# Digital_Inputs.net
KiCad netlist of a schematic drawn in Altium Designer
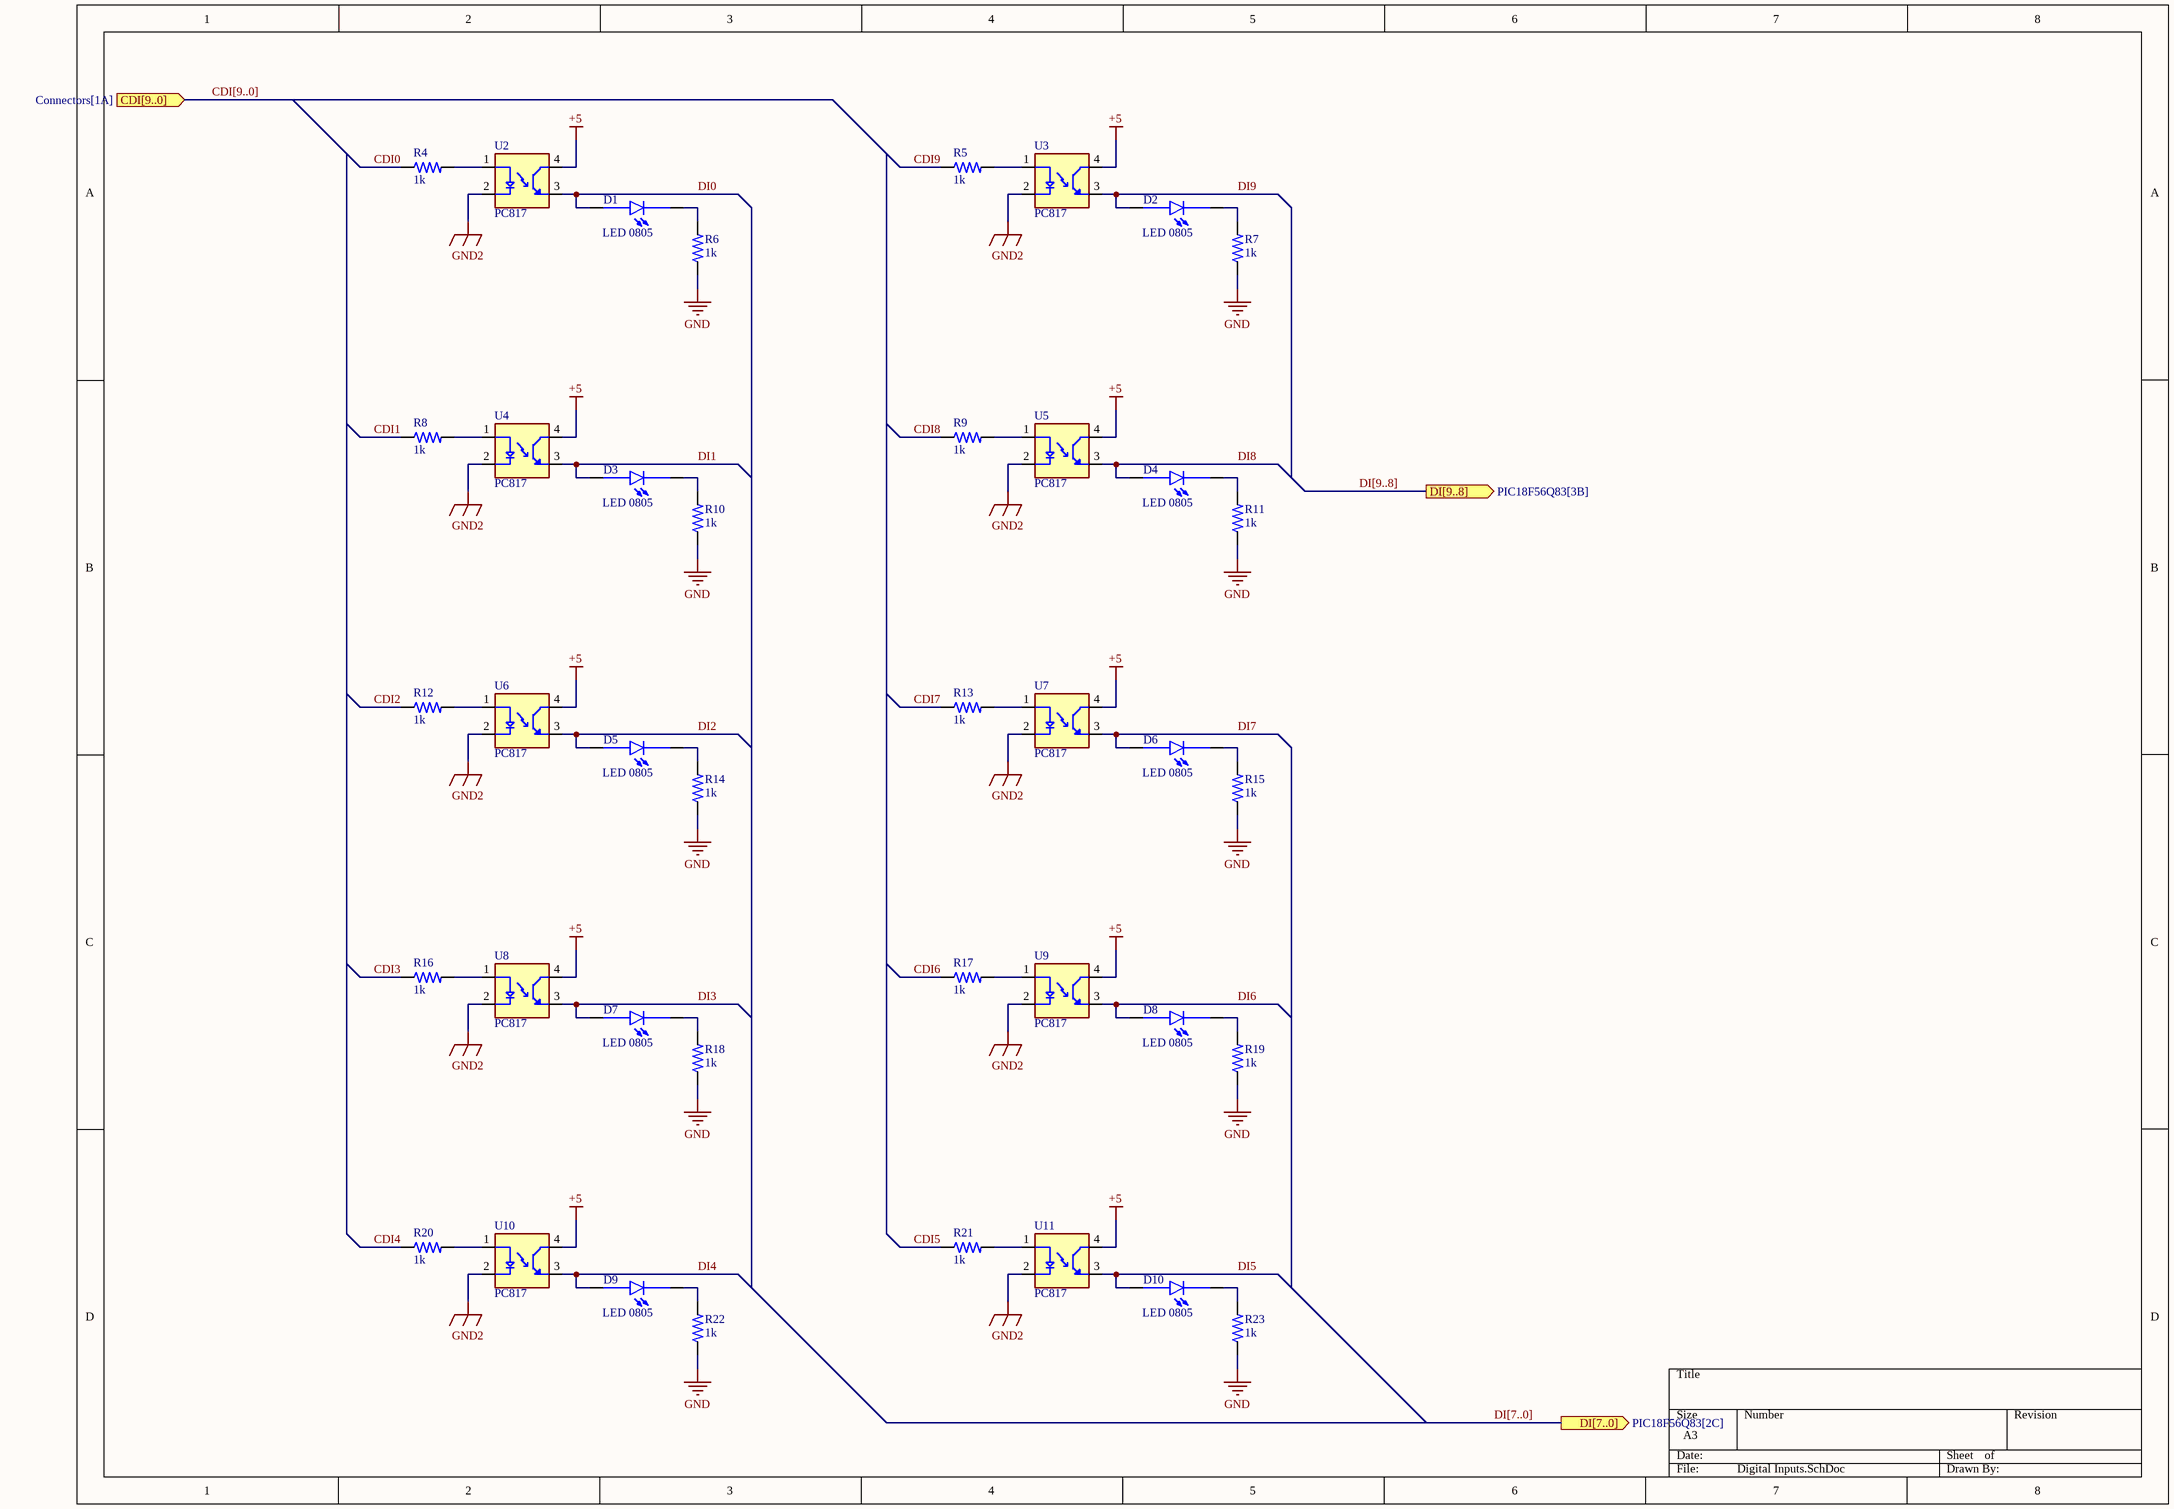
[diagram p0: Digital Inputs.SchDoc]

(export (version "E")
  (design (tool "Eeschema 10.0.6"))
  (components
    (comp (ref "D1")
      (value "LED 0805")
      (footprint "LED 0805")
      (description "LED Uni-Color Green 4-Pin Chip 0805 T/R")
      (fields (field (name "MP") "597-3305-607F"))
      (libsource (lib "LEDs SMD") (part "LED 0805"))
    )
    (comp (ref "D2")
      (value "LED 0805")
      (footprint "LED 0805")
      (description "LED Uni-Color Green 4-Pin Chip 0805 T/R")
      (fields (field (name "MP") "597-3305-607F"))
      (libsource (lib "LEDs SMD") (part "LED 0805"))
    )
    (comp (ref "D3")
      (value "LED 0805")
      (footprint "LED 0805")
      (description "LED Uni-Color Green 4-Pin Chip 0805 T/R")
      (fields (field (name "MP") "597-3305-607F"))
      (libsource (lib "LEDs SMD") (part "LED 0805"))
    )
    (comp (ref "D4")
      (value "LED 0805")
      (footprint "LED 0805")
      (description "LED Uni-Color Green 4-Pin Chip 0805 T/R")
      (fields (field (name "MP") "597-3305-607F"))
      (libsource (lib "LEDs SMD") (part "LED 0805"))
    )
    (comp (ref "D5")
      (value "LED 0805")
      (footprint "LED 0805")
      (description "LED Uni-Color Green 4-Pin Chip 0805 T/R")
      (fields (field (name "MP") "597-3305-607F"))
      (libsource (lib "LEDs SMD") (part "LED 0805"))
    )
    (comp (ref "D6")
      (value "LED 0805")
      (footprint "LED 0805")
      (description "LED Uni-Color Green 4-Pin Chip 0805 T/R")
      (fields (field (name "MP") "597-3305-607F"))
      (libsource (lib "LEDs SMD") (part "LED 0805"))
    )
    (comp (ref "D7")
      (value "LED 0805")
      (footprint "LED 0805")
      (description "LED Uni-Color Green 4-Pin Chip 0805 T/R")
      (fields (field (name "MP") "597-3305-607F"))
      (libsource (lib "LEDs SMD") (part "LED 0805"))
    )
    (comp (ref "D8")
      (value "LED 0805")
      (footprint "LED 0805")
      (description "LED Uni-Color Green 4-Pin Chip 0805 T/R")
      (fields (field (name "MP") "597-3305-607F"))
      (libsource (lib "LEDs SMD") (part "LED 0805"))
    )
    (comp (ref "D9")
      (value "LED 0805")
      (footprint "LED 0805")
      (description "LED Uni-Color Green 4-Pin Chip 0805 T/R")
      (fields (field (name "MP") "597-3305-607F"))
      (libsource (lib "LEDs SMD") (part "LED 0805"))
    )
    (comp (ref "D10")
      (value "LED 0805")
      (footprint "LED 0805")
      (description "LED Uni-Color Green 4-Pin Chip 0805 T/R")
      (fields (field (name "MP") "597-3305-607F"))
      (libsource (lib "LEDs SMD") (part "LED 0805"))
    )
    (comp (ref "R4")
      (value "1k")
      (footprint "0805")
      (fields
        (field (name "MP") "2-2176053-0")
        (field (name "TOLERANCE") "1%")
        (field (name "MF") "TE Connectivity")
      )
      (libsource (lib "Resistors SMD") (part "0805_Resistor"))
    )
    (comp (ref "R5")
      (value "1k")
      (footprint "0805")
      (fields
        (field (name "MP") "2-2176053-0")
        (field (name "TOLERANCE") "1%")
        (field (name "MF") "TE Connectivity")
      )
      (libsource (lib "Resistors SMD") (part "0805_Resistor"))
    )
    (comp (ref "R6")
      (value "1k")
      (footprint "0805")
      (fields
        (field (name "MP") "2-2176053-0")
        (field (name "TOLERANCE") "1%")
        (field (name "MF") "TE Connectivity")
      )
      (libsource (lib "Resistors SMD") (part "0805_Resistor"))
    )
    (comp (ref "R7")
      (value "1k")
      (footprint "0805")
      (fields
        (field (name "MP") "2-2176053-0")
        (field (name "TOLERANCE") "1%")
        (field (name "MF") "TE Connectivity")
      )
      (libsource (lib "Resistors SMD") (part "0805_Resistor"))
    )
    (comp (ref "R8")
      (value "1k")
      (footprint "0805")
      (fields
        (field (name "MP") "2-2176053-0")
        (field (name "TOLERANCE") "1%")
        (field (name "MF") "TE Connectivity")
      )
      (libsource (lib "Resistors SMD") (part "0805_Resistor"))
    )
    (comp (ref "R9")
      (value "1k")
      (footprint "0805")
      (fields
        (field (name "MP") "2-2176053-0")
        (field (name "TOLERANCE") "1%")
        (field (name "MF") "TE Connectivity")
      )
      (libsource (lib "Resistors SMD") (part "0805_Resistor"))
    )
    (comp (ref "R10")
      (value "1k")
      (footprint "0805")
      (fields
        (field (name "MP") "2-2176053-0")
        (field (name "TOLERANCE") "1%")
        (field (name "MF") "TE Connectivity")
      )
      (libsource (lib "Resistors SMD") (part "0805_Resistor"))
    )
    (comp (ref "R11")
      (value "1k")
      (footprint "0805")
      (fields
        (field (name "MP") "2-2176053-0")
        (field (name "TOLERANCE") "1%")
        (field (name "MF") "TE Connectivity")
      )
      (libsource (lib "Resistors SMD") (part "0805_Resistor"))
    )
    (comp (ref "R12")
      (value "1k")
      (footprint "0805")
      (fields
        (field (name "MP") "2-2176053-0")
        (field (name "TOLERANCE") "1%")
        (field (name "MF") "TE Connectivity")
      )
      (libsource (lib "Resistors SMD") (part "0805_Resistor"))
    )
    (comp (ref "R13")
      (value "1k")
      (footprint "0805")
      (fields
        (field (name "MP") "2-2176053-0")
        (field (name "TOLERANCE") "1%")
        (field (name "MF") "TE Connectivity")
      )
      (libsource (lib "Resistors SMD") (part "0805_Resistor"))
    )
    (comp (ref "R14")
      (value "1k")
      (footprint "0805")
      (fields
        (field (name "MP") "2-2176053-0")
        (field (name "TOLERANCE") "1%")
        (field (name "MF") "TE Connectivity")
      )
      (libsource (lib "Resistors SMD") (part "0805_Resistor"))
    )
    (comp (ref "R15")
      (value "1k")
      (footprint "0805")
      (fields
        (field (name "MP") "2-2176053-0")
        (field (name "TOLERANCE") "1%")
        (field (name "MF") "TE Connectivity")
      )
      (libsource (lib "Resistors SMD") (part "0805_Resistor"))
    )
    (comp (ref "R16")
      (value "1k")
      (footprint "0805")
      (fields
        (field (name "MP") "2-2176053-0")
        (field (name "TOLERANCE") "1%")
        (field (name "MF") "TE Connectivity")
      )
      (libsource (lib "Resistors SMD") (part "0805_Resistor"))
    )
    (comp (ref "R17")
      (value "1k")
      (footprint "0805")
      (fields
        (field (name "MP") "2-2176053-0")
        (field (name "TOLERANCE") "1%")
        (field (name "MF") "TE Connectivity")
      )
      (libsource (lib "Resistors SMD") (part "0805_Resistor"))
    )
    (comp (ref "R18")
      (value "1k")
      (footprint "0805")
      (fields
        (field (name "MP") "2-2176053-0")
        (field (name "TOLERANCE") "1%")
        (field (name "MF") "TE Connectivity")
      )
      (libsource (lib "Resistors SMD") (part "0805_Resistor"))
    )
    (comp (ref "R19")
      (value "1k")
      (footprint "0805")
      (fields
        (field (name "MP") "2-2176053-0")
        (field (name "TOLERANCE") "1%")
        (field (name "MF") "TE Connectivity")
      )
      (libsource (lib "Resistors SMD") (part "0805_Resistor"))
    )
    (comp (ref "R20")
      (value "1k")
      (footprint "0805")
      (fields
        (field (name "MP") "2-2176053-0")
        (field (name "TOLERANCE") "1%")
        (field (name "MF") "TE Connectivity")
      )
      (libsource (lib "Resistors SMD") (part "0805_Resistor"))
    )
    (comp (ref "R21")
      (value "1k")
      (footprint "0805")
      (fields
        (field (name "MP") "2-2176053-0")
        (field (name "TOLERANCE") "1%")
        (field (name "MF") "TE Connectivity")
      )
      (libsource (lib "Resistors SMD") (part "0805_Resistor"))
    )
    (comp (ref "R22")
      (value "1k")
      (footprint "0805")
      (fields
        (field (name "MP") "2-2176053-0")
        (field (name "TOLERANCE") "1%")
        (field (name "MF") "TE Connectivity")
      )
      (libsource (lib "Resistors SMD") (part "0805_Resistor"))
    )
    (comp (ref "R23")
      (value "1k")
      (footprint "0805")
      (fields
        (field (name "MP") "2-2176053-0")
        (field (name "TOLERANCE") "1%")
        (field (name "MF") "TE Connectivity")
      )
      (libsource (lib "Resistors SMD") (part "0805_Resistor"))
    )
    (comp (ref "U2")
      (value "PC817")
      (footprint "PC817")
      (description "Optoisolator Transistor Output 5000Vrms 1 Channel 4-SMD")
      (fields (field (name "MP") "PC817XI") (field (name "MF") "Sharp Microelectronics"))
      (libsource (lib "Optocoupler SMD") (part "PC817"))
    )
    (comp (ref "U3")
      (value "PC817")
      (footprint "PC817")
      (description "Optoisolator Transistor Output 5000Vrms 1 Channel 4-SMD")
      (fields (field (name "MP") "PC817XI") (field (name "MF") "Sharp Microelectronics"))
      (libsource (lib "Optocoupler SMD") (part "PC817"))
    )
    (comp (ref "U4")
      (value "PC817")
      (footprint "PC817")
      (description "Optoisolator Transistor Output 5000Vrms 1 Channel 4-SMD")
      (fields (field (name "MP") "PC817XI") (field (name "MF") "Sharp Microelectronics"))
      (libsource (lib "Optocoupler SMD") (part "PC817"))
    )
    (comp (ref "U5")
      (value "PC817")
      (footprint "PC817")
      (description "Optoisolator Transistor Output 5000Vrms 1 Channel 4-SMD")
      (fields (field (name "MP") "PC817XI") (field (name "MF") "Sharp Microelectronics"))
      (libsource (lib "Optocoupler SMD") (part "PC817"))
    )
    (comp (ref "U6")
      (value "PC817")
      (footprint "PC817")
      (description "Optoisolator Transistor Output 5000Vrms 1 Channel 4-SMD")
      (fields (field (name "MP") "PC817XI") (field (name "MF") "Sharp Microelectronics"))
      (libsource (lib "Optocoupler SMD") (part "PC817"))
    )
    (comp (ref "U7")
      (value "PC817")
      (footprint "PC817")
      (description "Optoisolator Transistor Output 5000Vrms 1 Channel 4-SMD")
      (fields (field (name "MP") "PC817XI") (field (name "MF") "Sharp Microelectronics"))
      (libsource (lib "Optocoupler SMD") (part "PC817"))
    )
    (comp (ref "U8")
      (value "PC817")
      (footprint "PC817")
      (description "Optoisolator Transistor Output 5000Vrms 1 Channel 4-SMD")
      (fields (field (name "MP") "PC817XI") (field (name "MF") "Sharp Microelectronics"))
      (libsource (lib "Optocoupler SMD") (part "PC817"))
    )
    (comp (ref "U9")
      (value "PC817")
      (footprint "PC817")
      (description "Optoisolator Transistor Output 5000Vrms 1 Channel 4-SMD")
      (fields (field (name "MP") "PC817XI") (field (name "MF") "Sharp Microelectronics"))
      (libsource (lib "Optocoupler SMD") (part "PC817"))
    )
    (comp (ref "U10")
      (value "PC817")
      (footprint "PC817")
      (description "Optoisolator Transistor Output 5000Vrms 1 Channel 4-SMD")
      (fields (field (name "MP") "PC817XI") (field (name "MF") "Sharp Microelectronics"))
      (libsource (lib "Optocoupler SMD") (part "PC817"))
    )
    (comp (ref "U11")
      (value "PC817")
      (footprint "PC817")
      (description "Optoisolator Transistor Output 5000Vrms 1 Channel 4-SMD")
      (fields (field (name "MP") "PC817XI") (field (name "MF") "Sharp Microelectronics"))
      (libsource (lib "Optocoupler SMD") (part "PC817"))
    )
  )
  (nets
    (net (code "1") (name "+5") (class "Default")
      (node (ref "U10") (pin "4") (pinfunction "CT_4") (pintype "passive"))
      (node (ref "U11") (pin "4") (pinfunction "CT_4") (pintype "passive"))
      (node (ref "U2") (pin "4") (pinfunction "CT_4") (pintype "passive"))
      (node (ref "U3") (pin "4") (pinfunction "CT_4") (pintype "passive"))
      (node (ref "U4") (pin "4") (pinfunction "CT_4") (pintype "passive"))
      (node (ref "U5") (pin "4") (pinfunction "CT_4") (pintype "passive"))
      (node (ref "U6") (pin "4") (pinfunction "CT_4") (pintype "passive"))
      (node (ref "U7") (pin "4") (pinfunction "CT_4") (pintype "passive"))
      (node (ref "U8") (pin "4") (pinfunction "CT_4") (pintype "passive"))
      (node (ref "U9") (pin "4") (pinfunction "CT_4") (pintype "passive"))
    )
    (net (code "2") (name "/CDI0") (class "Default")
      (node (ref "R4") (pin "1") (pinfunction "1_1") (pintype "passive"))
    )
    (net (code "3") (name "/CDI1") (class "Default")
      (node (ref "R8") (pin "1") (pinfunction "1_1") (pintype "passive"))
    )
    (net (code "4") (name "/CDI2") (class "Default")
      (node (ref "R12") (pin "1") (pinfunction "1_1") (pintype "passive"))
    )
    (net (code "5") (name "/CDI3") (class "Default")
      (node (ref "R16") (pin "1") (pinfunction "1_1") (pintype "passive"))
    )
    (net (code "6") (name "/CDI4") (class "Default")
      (node (ref "R20") (pin "1") (pinfunction "1_1") (pintype "passive"))
    )
    (net (code "7") (name "/CDI5") (class "Default")
      (node (ref "R21") (pin "1") (pinfunction "1_1") (pintype "passive"))
    )
    (net (code "8") (name "/CDI6") (class "Default")
      (node (ref "R17") (pin "1") (pinfunction "1_1") (pintype "passive"))
    )
    (net (code "9") (name "/CDI7") (class "Default")
      (node (ref "R13") (pin "1") (pinfunction "1_1") (pintype "passive"))
    )
    (net (code "10") (name "/CDI8") (class "Default")
      (node (ref "R9") (pin "1") (pinfunction "1_1") (pintype "passive"))
    )
    (net (code "11") (name "/CDI9") (class "Default")
      (node (ref "R5") (pin "1") (pinfunction "1_1") (pintype "passive"))
    )
    (net (code "13") (name "/DI0") (class "Default")
      (node (ref "D1") (pin "A") (pinfunction "A_A") (pintype "passive"))
      (node (ref "U2") (pin "3") (pinfunction "ET_3") (pintype "passive"))
    )
    (net (code "14") (name "/DI1") (class "Default")
      (node (ref "D3") (pin "A") (pinfunction "A_A") (pintype "passive"))
      (node (ref "U4") (pin "3") (pinfunction "ET_3") (pintype "passive"))
    )
    (net (code "15") (name "/DI2") (class "Default")
      (node (ref "D5") (pin "A") (pinfunction "A_A") (pintype "passive"))
      (node (ref "U6") (pin "3") (pinfunction "ET_3") (pintype "passive"))
    )
    (net (code "16") (name "/DI3") (class "Default")
      (node (ref "D7") (pin "A") (pinfunction "A_A") (pintype "passive"))
      (node (ref "U8") (pin "3") (pinfunction "ET_3") (pintype "passive"))
    )
    (net (code "17") (name "/DI4") (class "Default")
      (node (ref "D9") (pin "A") (pinfunction "A_A") (pintype "passive"))
      (node (ref "U10") (pin "3") (pinfunction "ET_3") (pintype "passive"))
    )
    (net (code "18") (name "/DI5") (class "Default")
      (node (ref "D10") (pin "A") (pinfunction "A_A") (pintype "passive"))
      (node (ref "U11") (pin "3") (pinfunction "ET_3") (pintype "passive"))
    )
    (net (code "19") (name "/DI6") (class "Default")
      (node (ref "D8") (pin "A") (pinfunction "A_A") (pintype "passive"))
      (node (ref "U9") (pin "3") (pinfunction "ET_3") (pintype "passive"))
    )
    (net (code "20") (name "/DI7") (class "Default")
      (node (ref "D6") (pin "A") (pinfunction "A_A") (pintype "passive"))
      (node (ref "U7") (pin "3") (pinfunction "ET_3") (pintype "passive"))
    )
    (net (code "21") (name "/DI8") (class "Default")
      (node (ref "D4") (pin "A") (pinfunction "A_A") (pintype "passive"))
      (node (ref "U5") (pin "3") (pinfunction "ET_3") (pintype "passive"))
    )
    (net (code "22") (name "/DI9") (class "Default")
      (node (ref "D2") (pin "A") (pinfunction "A_A") (pintype "passive"))
      (node (ref "U3") (pin "3") (pinfunction "ET_3") (pintype "passive"))
    )
    (net (code "25") (name "GND") (class "Default")
      (node (ref "R10") (pin "1") (pinfunction "1_1") (pintype "passive"))
      (node (ref "R11") (pin "1") (pinfunction "1_1") (pintype "passive"))
      (node (ref "R14") (pin "1") (pinfunction "1_1") (pintype "passive"))
      (node (ref "R15") (pin "1") (pinfunction "1_1") (pintype "passive"))
      (node (ref "R18") (pin "1") (pinfunction "1_1") (pintype "passive"))
      (node (ref "R19") (pin "1") (pinfunction "1_1") (pintype "passive"))
      (node (ref "R22") (pin "1") (pinfunction "1_1") (pintype "passive"))
      (node (ref "R23") (pin "1") (pinfunction "1_1") (pintype "passive"))
      (node (ref "R6") (pin "1") (pinfunction "1_1") (pintype "passive"))
      (node (ref "R7") (pin "1") (pinfunction "1_1") (pintype "passive"))
    )
    (net (code "26") (name "GND2") (class "Default")
      (node (ref "U10") (pin "2") (pinfunction "C_2") (pintype "passive"))
      (node (ref "U11") (pin "2") (pinfunction "C_2") (pintype "passive"))
      (node (ref "U2") (pin "2") (pinfunction "C_2") (pintype "passive"))
      (node (ref "U3") (pin "2") (pinfunction "C_2") (pintype "passive"))
      (node (ref "U4") (pin "2") (pinfunction "C_2") (pintype "passive"))
      (node (ref "U5") (pin "2") (pinfunction "C_2") (pintype "passive"))
      (node (ref "U6") (pin "2") (pinfunction "C_2") (pintype "passive"))
      (node (ref "U7") (pin "2") (pinfunction "C_2") (pintype "passive"))
      (node (ref "U8") (pin "2") (pinfunction "C_2") (pintype "passive"))
      (node (ref "U9") (pin "2") (pinfunction "C_2") (pintype "passive"))
    )
    (net (code "27") (name "Net-(D1-PadC)") (class "Default")
      (node (ref "D1") (pin "C") (pinfunction "C_C") (pintype "passive"))
      (node (ref "R6") (pin "2") (pinfunction "2_2") (pintype "passive"))
    )
    (net (code "28") (name "Net-(D2-PadC)") (class "Default")
      (node (ref "D2") (pin "C") (pinfunction "C_C") (pintype "passive"))
      (node (ref "R7") (pin "2") (pinfunction "2_2") (pintype "passive"))
    )
    (net (code "29") (name "Net-(D3-PadC)") (class "Default")
      (node (ref "D3") (pin "C") (pinfunction "C_C") (pintype "passive"))
      (node (ref "R10") (pin "2") (pinfunction "2_2") (pintype "passive"))
    )
    (net (code "30") (name "Net-(D4-PadC)") (class "Default")
      (node (ref "D4") (pin "C") (pinfunction "C_C") (pintype "passive"))
      (node (ref "R11") (pin "2") (pinfunction "2_2") (pintype "passive"))
    )
    (net (code "31") (name "Net-(D5-PadC)") (class "Default")
      (node (ref "D5") (pin "C") (pinfunction "C_C") (pintype "passive"))
      (node (ref "R14") (pin "2") (pinfunction "2_2") (pintype "passive"))
    )
    (net (code "32") (name "Net-(D6-PadC)") (class "Default")
      (node (ref "D6") (pin "C") (pinfunction "C_C") (pintype "passive"))
      (node (ref "R15") (pin "2") (pinfunction "2_2") (pintype "passive"))
    )
    (net (code "33") (name "Net-(D7-PadC)") (class "Default")
      (node (ref "D7") (pin "C") (pinfunction "C_C") (pintype "passive"))
      (node (ref "R18") (pin "2") (pinfunction "2_2") (pintype "passive"))
    )
    (net (code "34") (name "Net-(D8-PadC)") (class "Default")
      (node (ref "D8") (pin "C") (pinfunction "C_C") (pintype "passive"))
      (node (ref "R19") (pin "2") (pinfunction "2_2") (pintype "passive"))
    )
    (net (code "35") (name "Net-(D9-PadC)") (class "Default")
      (node (ref "D9") (pin "C") (pinfunction "C_C") (pintype "passive"))
      (node (ref "R22") (pin "2") (pinfunction "2_2") (pintype "passive"))
    )
    (net (code "36") (name "Net-(D10-PadC)") (class "Default")
      (node (ref "D10") (pin "C") (pinfunction "C_C") (pintype "passive"))
      (node (ref "R23") (pin "2") (pinfunction "2_2") (pintype "passive"))
    )
    (net (code "37") (name "Net-(U2-A)") (class "Default")
      (node (ref "R4") (pin "2") (pinfunction "2_2") (pintype "passive"))
      (node (ref "U2") (pin "1") (pinfunction "A_1") (pintype "passive"))
    )
    (net (code "38") (name "Net-(U3-A)") (class "Default")
      (node (ref "R5") (pin "2") (pinfunction "2_2") (pintype "passive"))
      (node (ref "U3") (pin "1") (pinfunction "A_1") (pintype "passive"))
    )
    (net (code "39") (name "Net-(U4-A)") (class "Default")
      (node (ref "R8") (pin "2") (pinfunction "2_2") (pintype "passive"))
      (node (ref "U4") (pin "1") (pinfunction "A_1") (pintype "passive"))
    )
    (net (code "40") (name "Net-(U5-A)") (class "Default")
      (node (ref "R9") (pin "2") (pinfunction "2_2") (pintype "passive"))
      (node (ref "U5") (pin "1") (pinfunction "A_1") (pintype "passive"))
    )
    (net (code "41") (name "Net-(U6-A)") (class "Default")
      (node (ref "R12") (pin "2") (pinfunction "2_2") (pintype "passive"))
      (node (ref "U6") (pin "1") (pinfunction "A_1") (pintype "passive"))
    )
    (net (code "42") (name "Net-(U7-A)") (class "Default")
      (node (ref "R13") (pin "2") (pinfunction "2_2") (pintype "passive"))
      (node (ref "U7") (pin "1") (pinfunction "A_1") (pintype "passive"))
    )
    (net (code "43") (name "Net-(U8-A)") (class "Default")
      (node (ref "R16") (pin "2") (pinfunction "2_2") (pintype "passive"))
      (node (ref "U8") (pin "1") (pinfunction "A_1") (pintype "passive"))
    )
    (net (code "44") (name "Net-(U9-A)") (class "Default")
      (node (ref "R17") (pin "2") (pinfunction "2_2") (pintype "passive"))
      (node (ref "U9") (pin "1") (pinfunction "A_1") (pintype "passive"))
    )
    (net (code "45") (name "Net-(U10-A)") (class "Default")
      (node (ref "R20") (pin "2") (pinfunction "2_2") (pintype "passive"))
      (node (ref "U10") (pin "1") (pinfunction "A_1") (pintype "passive"))
    )
    (net (code "46") (name "Net-(U11-A)") (class "Default")
      (node (ref "R21") (pin "2") (pinfunction "2_2") (pintype "passive"))
      (node (ref "U11") (pin "1") (pinfunction "A_1") (pintype "passive"))
    )
  )
)
